# ESCON_Module_64.net
KiCad netlist of a schematic drawn in EAGLE
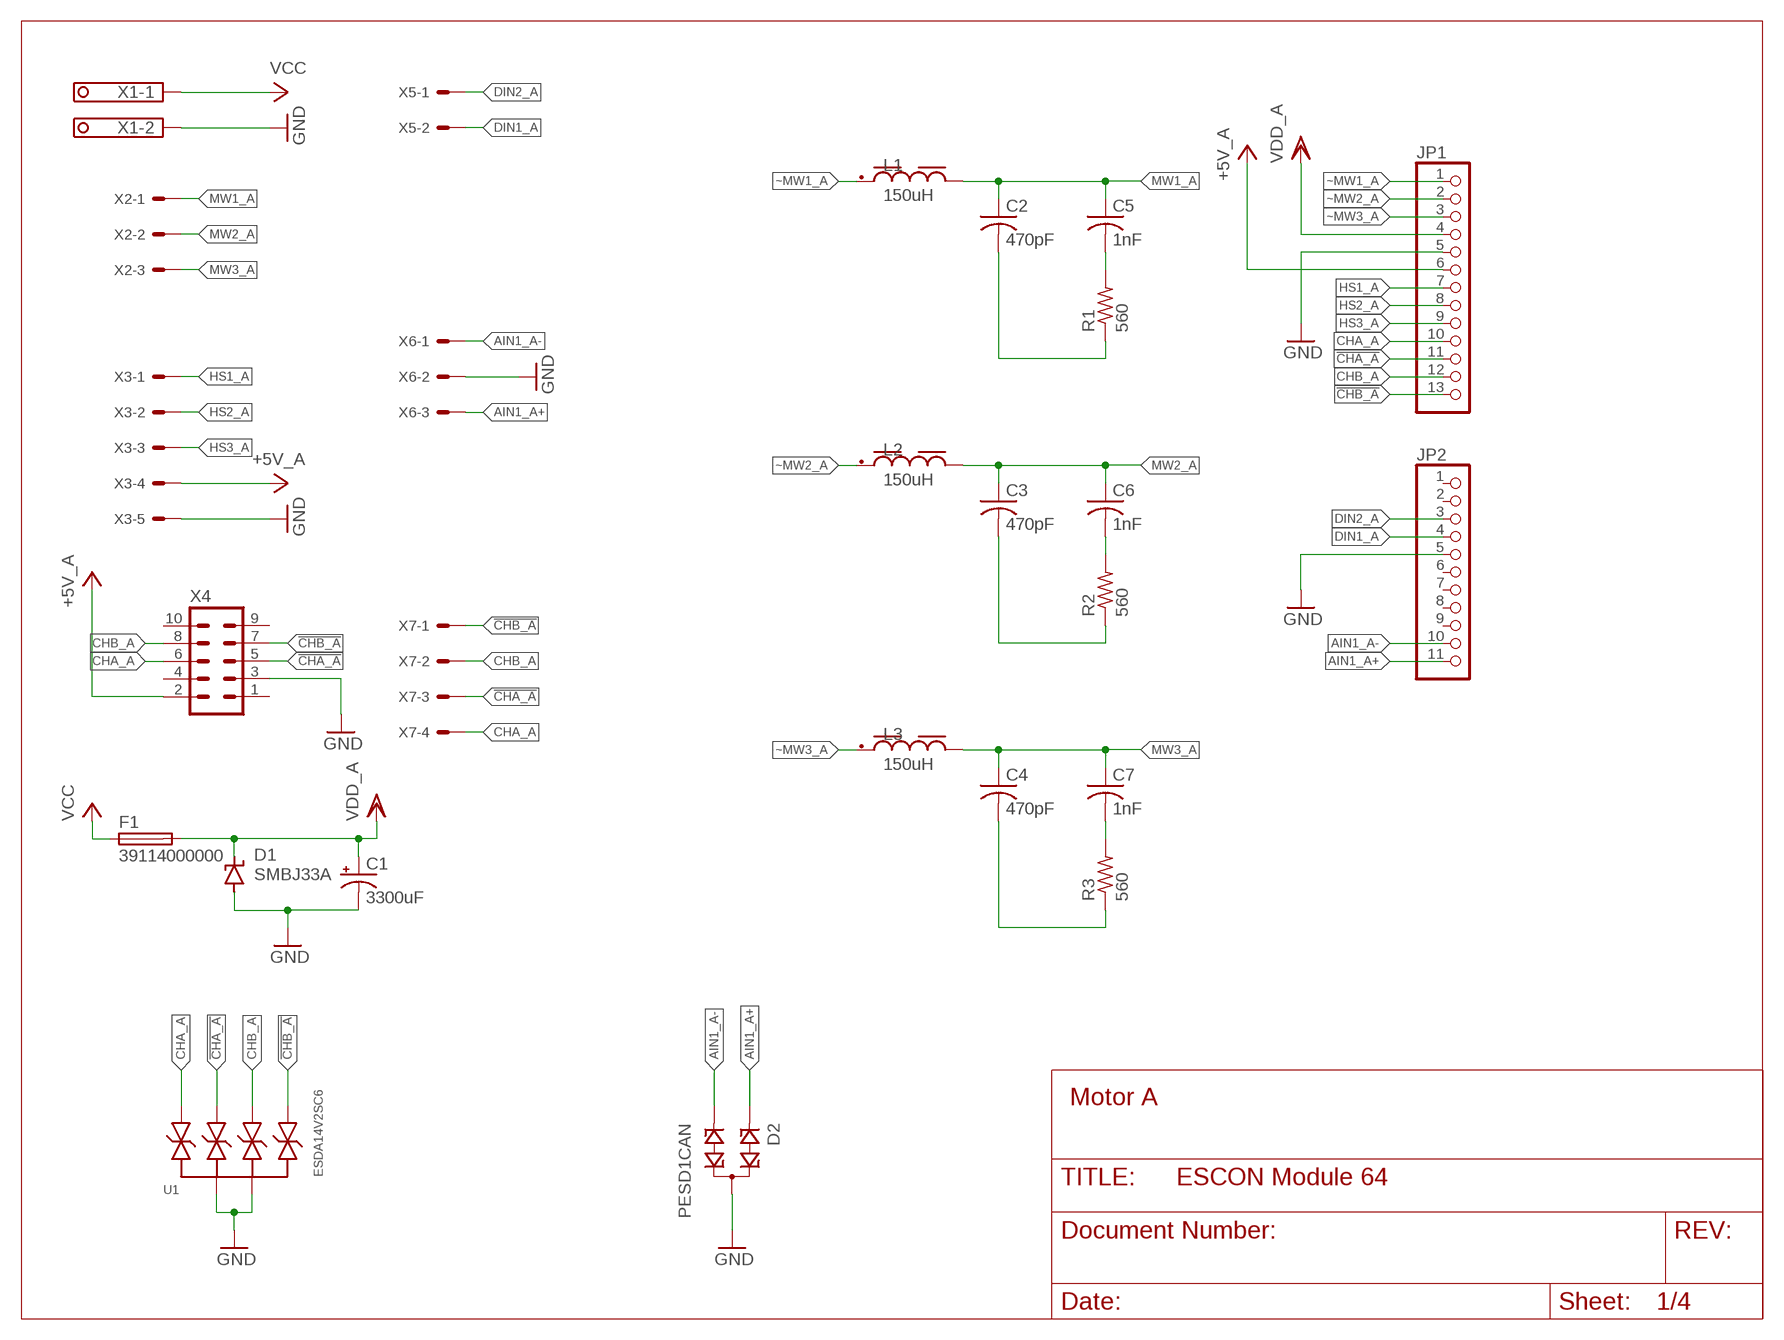
[diagram p0: schematic, sheet 1]
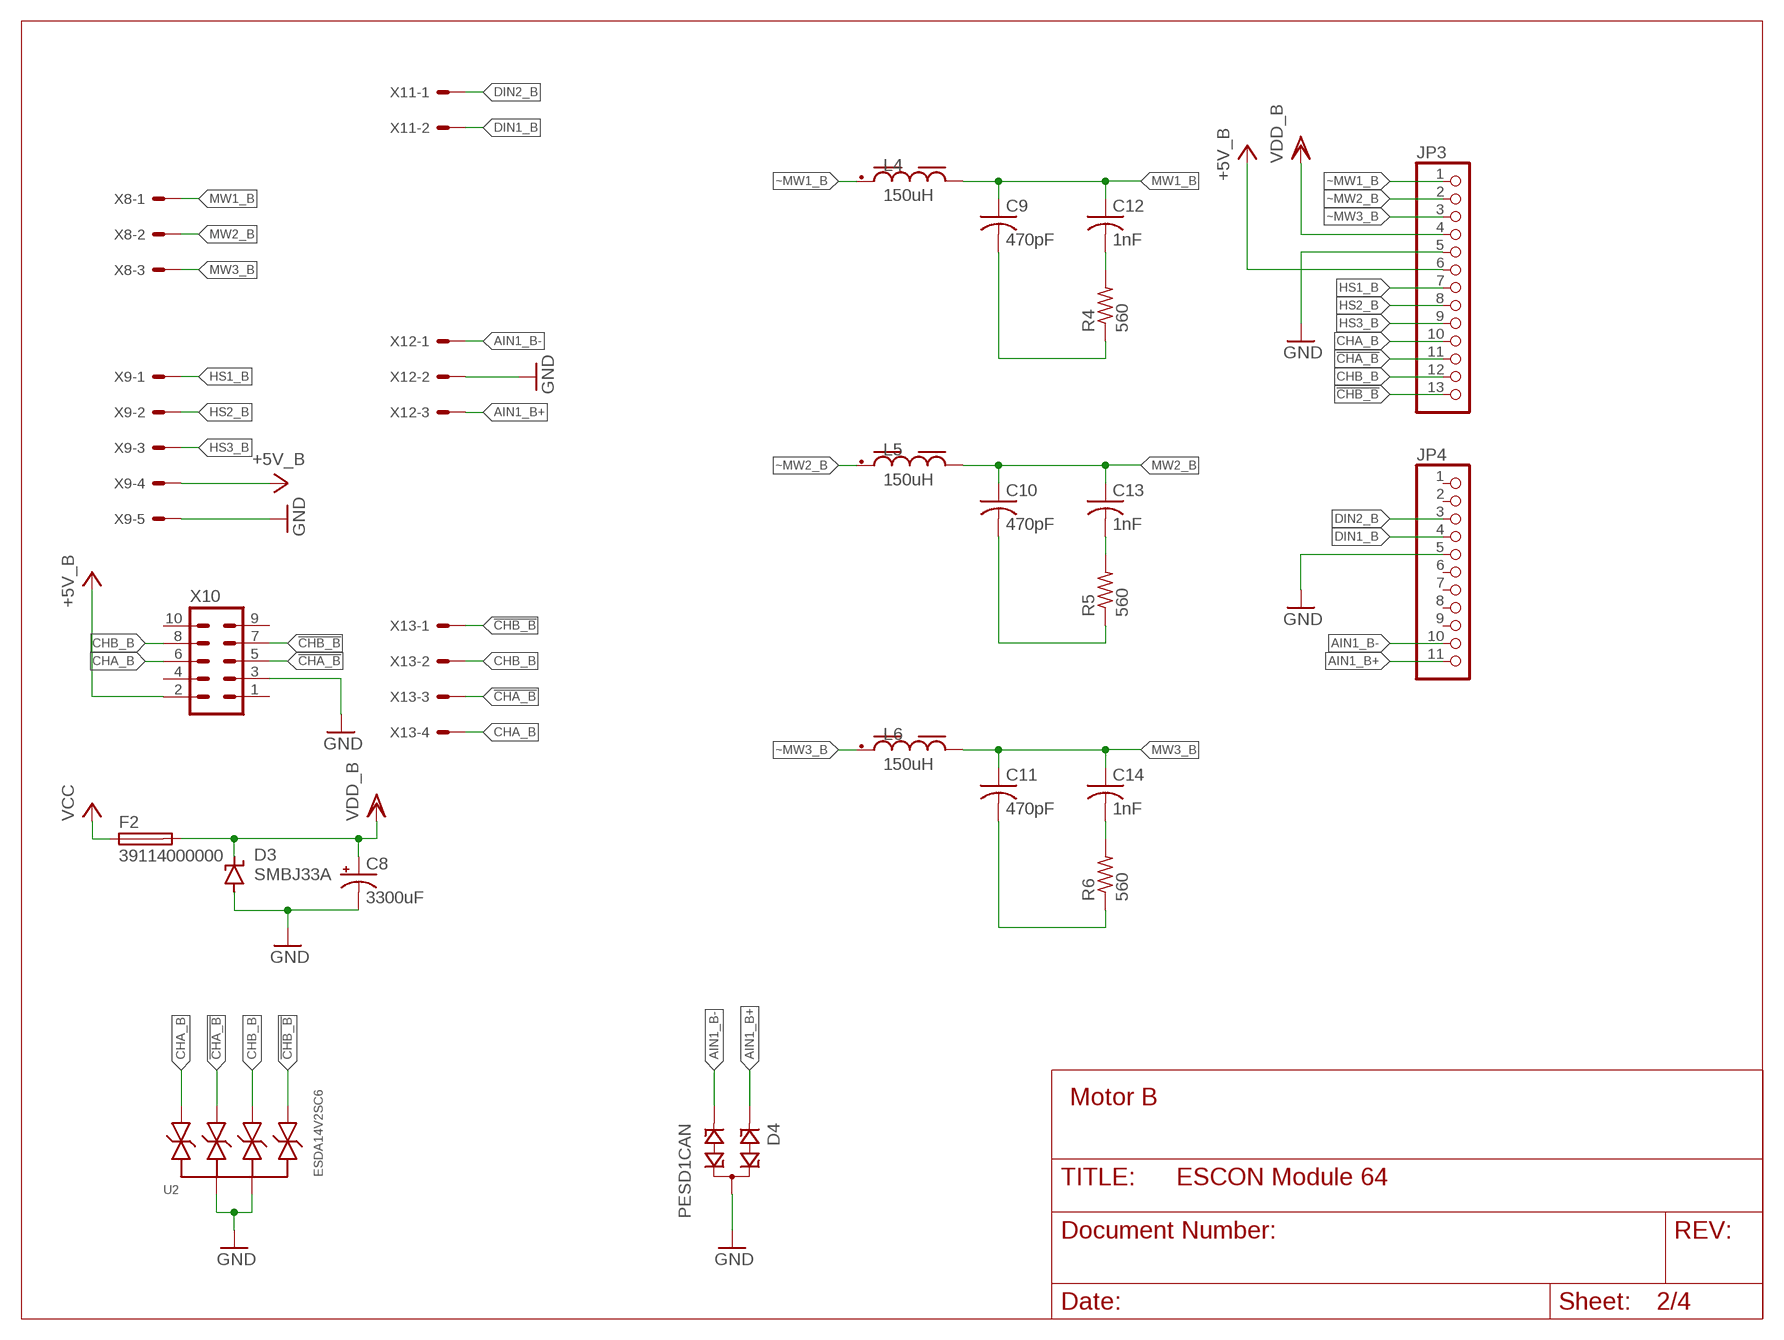
[diagram p1: schematic, sheet 2]
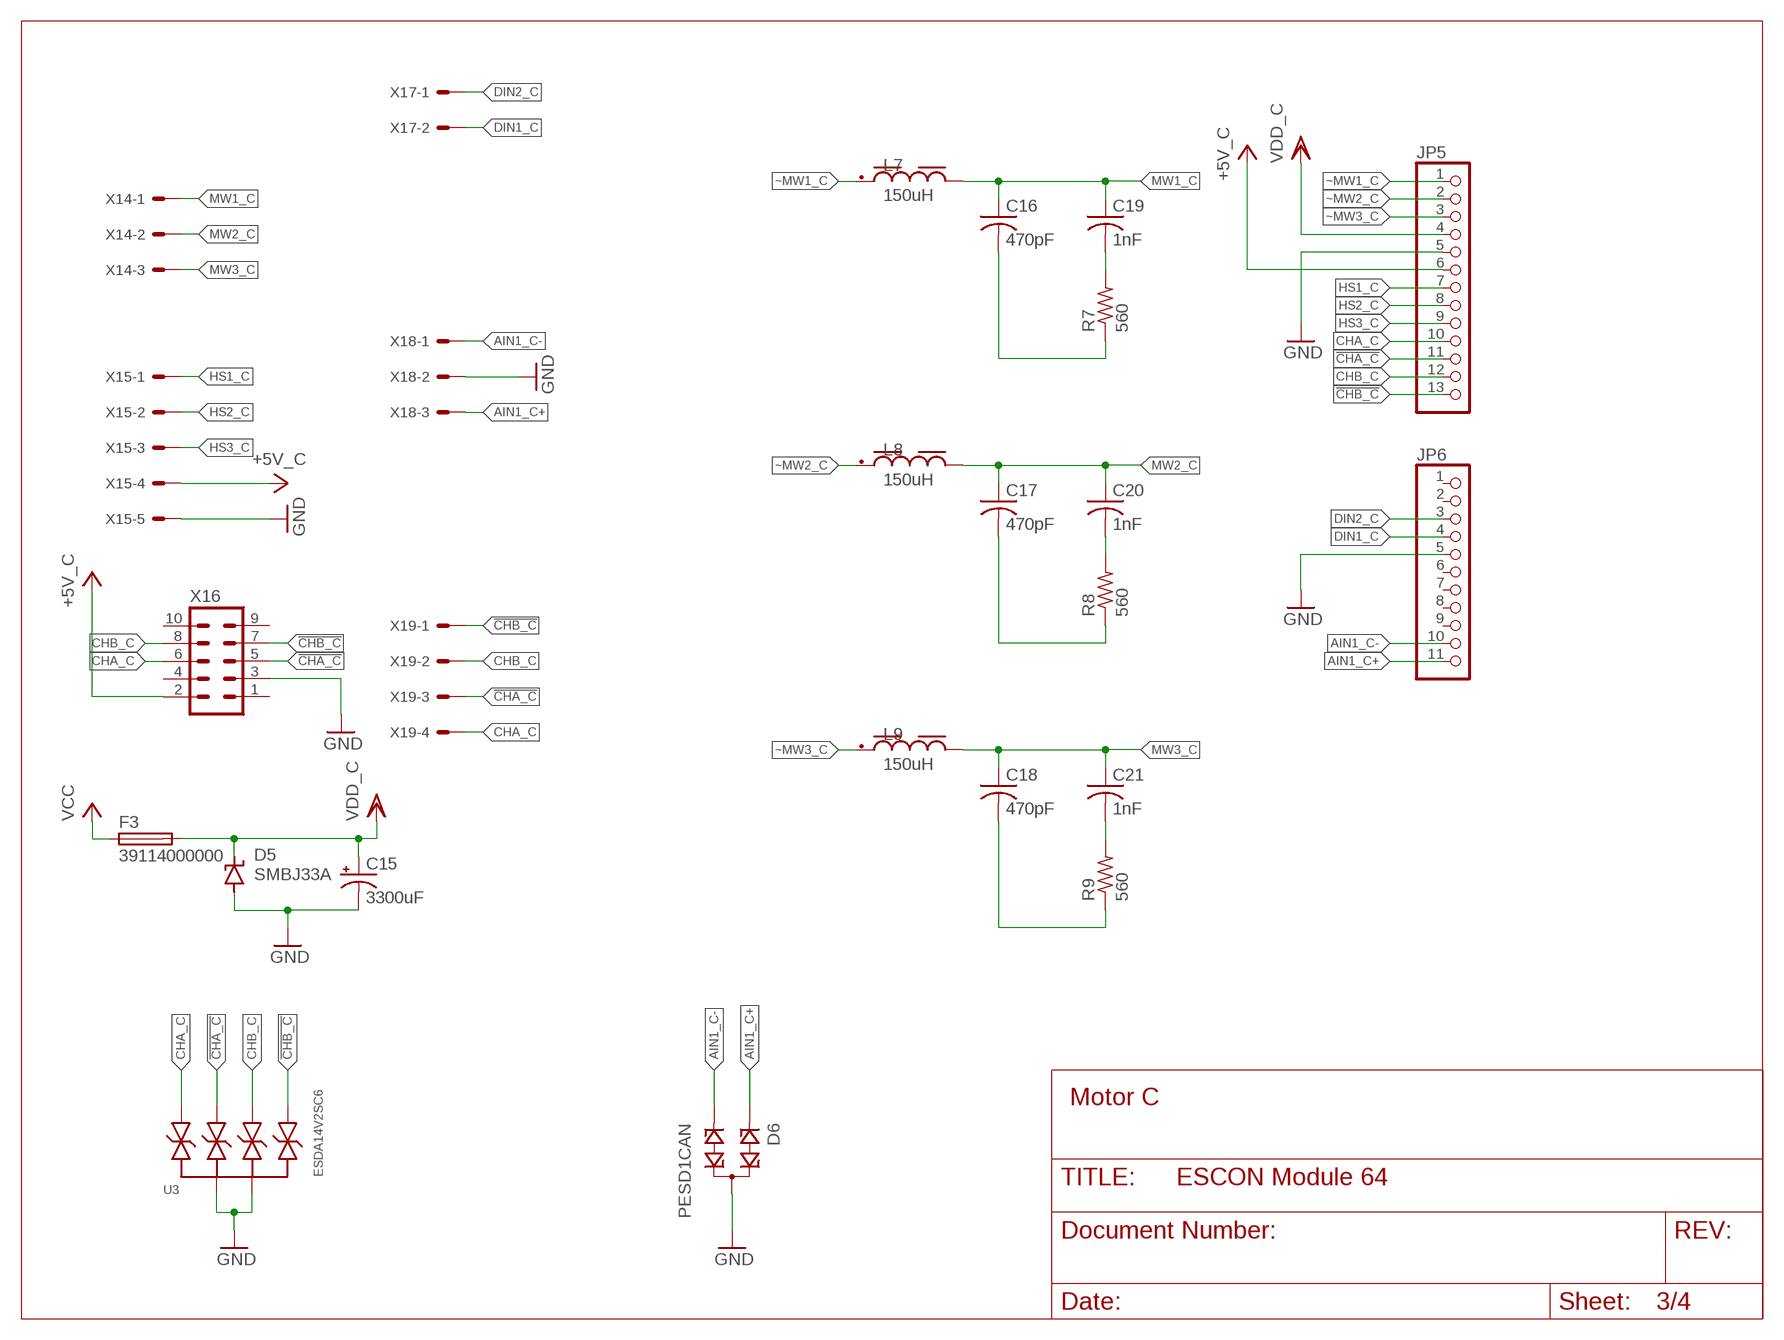
[diagram p2: schematic, sheet 3]
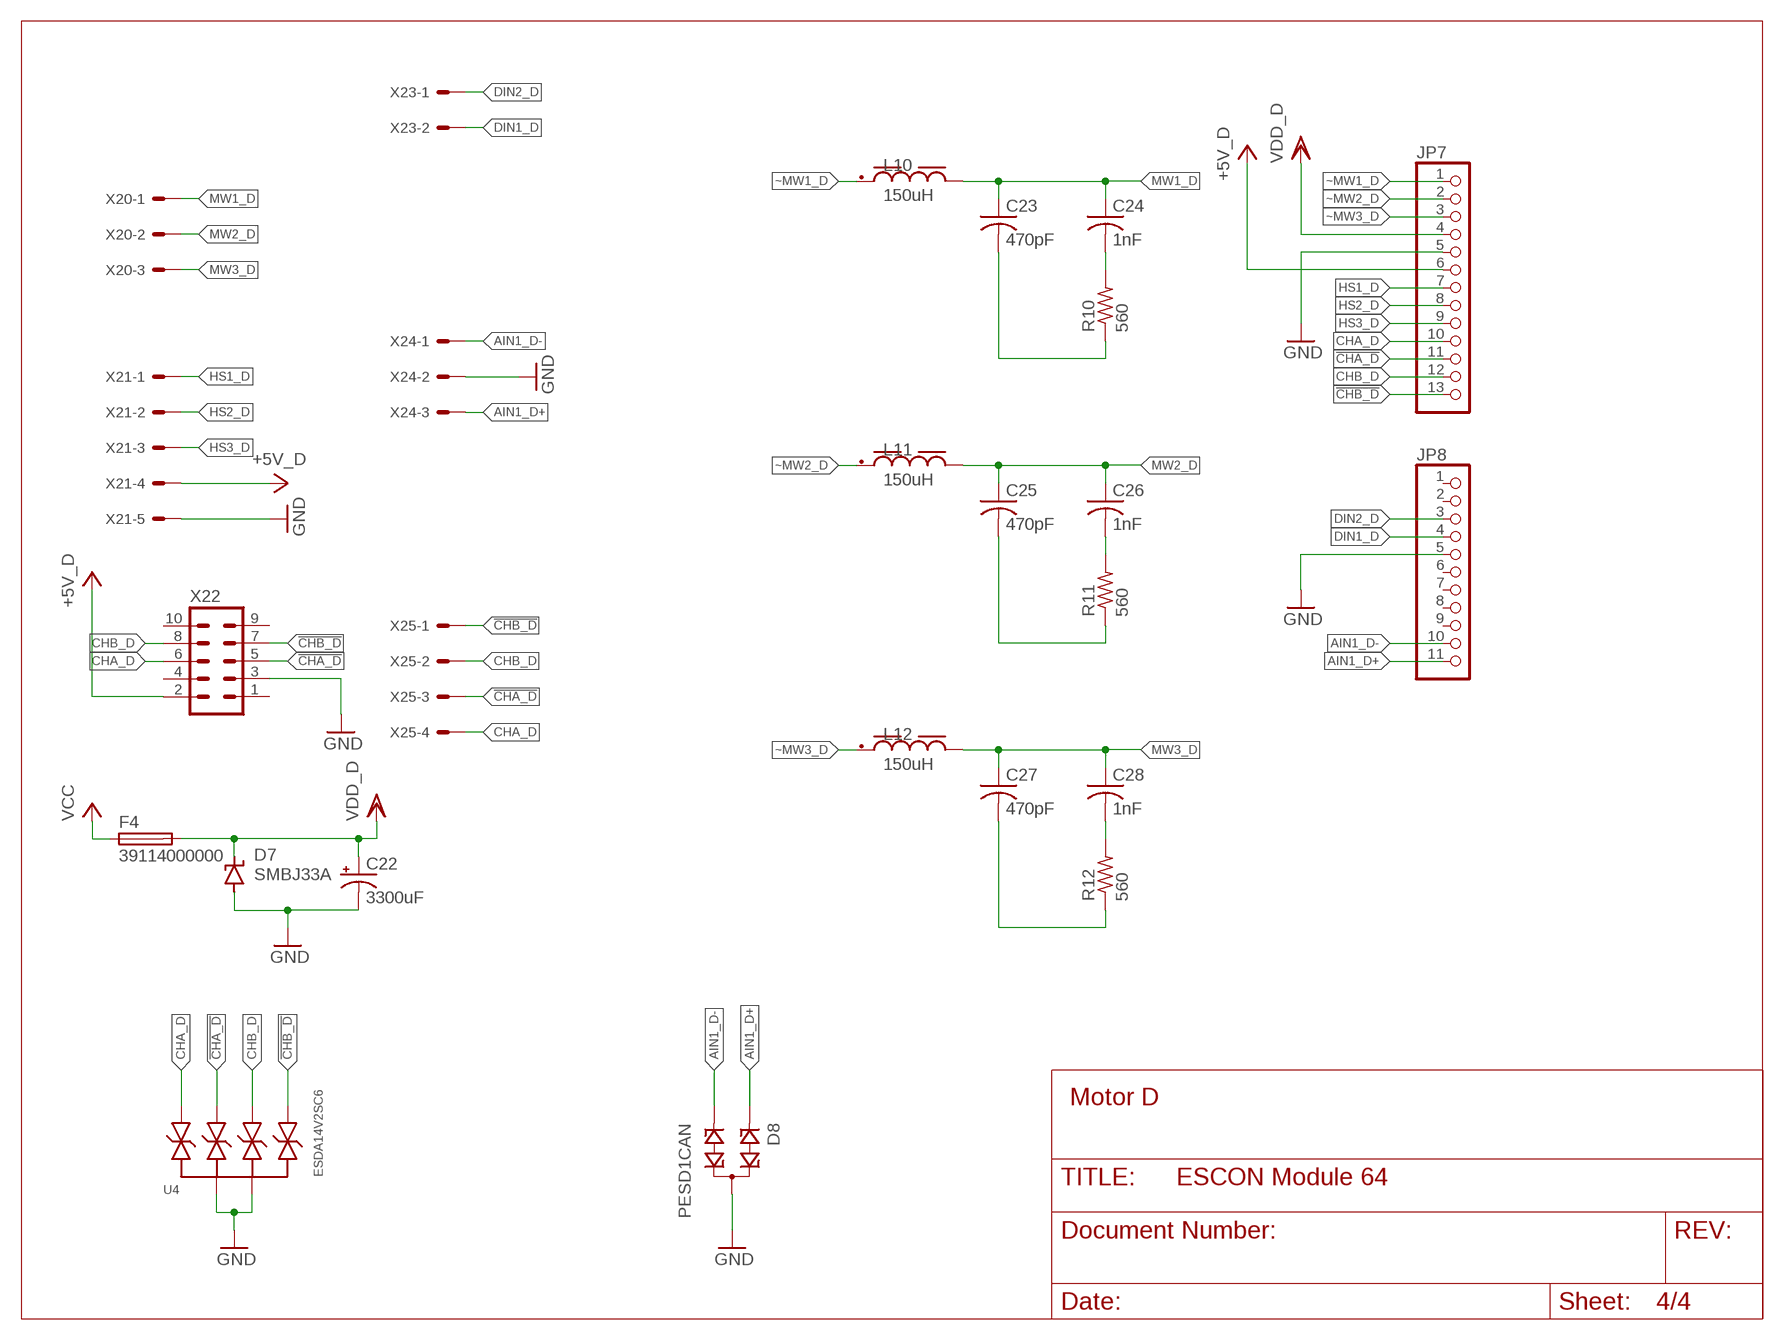
[diagram p3: schematic, sheet 4]

(export (version "E")
  (design (tool "Eeschema 10.0.6"))
  (components
    (comp (ref "C15")
      (value "3300uF")
      (footprint "eagle-import:E7,5-18")
      (libsource (lib "eagle-import") (part "CPOL-USE7.5-18"))
    )
    (comp (ref "C16")
      (value "470pF")
      (footprint "eagle-import:C0603")
      (libsource (lib "eagle-import") (part "C-USC0603"))
    )
    (comp (ref "C17")
      (value "470pF")
      (footprint "eagle-import:C0603")
      (libsource (lib "eagle-import") (part "C-USC0603"))
    )
    (comp (ref "C18")
      (value "470pF")
      (footprint "eagle-import:C0603")
      (libsource (lib "eagle-import") (part "C-USC0603"))
    )
    (comp (ref "C19")
      (value "1nF")
      (footprint "eagle-import:C0603")
      (libsource (lib "eagle-import") (part "C-USC0603"))
    )
    (comp (ref "C20")
      (value "1nF")
      (footprint "eagle-import:C0603")
      (libsource (lib "eagle-import") (part "C-USC0603"))
    )
    (comp (ref "C21")
      (value "1nF")
      (footprint "eagle-import:C0603")
      (libsource (lib "eagle-import") (part "C-USC0603"))
    )
    (comp (ref "D5")
      (value "SMBJ33A")
      (footprint "eagle-import:SMBJ")
      (libsource (lib "eagle-import") (part "SUPPRESSOR-SMBJ"))
    )
    (comp (ref "D6")
      (value "PESD1CAN")
      (footprint "eagle-import:SOT23")
      (libsource (lib "eagle-import") (part "PESD1CAN"))
    )
    (comp (ref "F3")
      (value "39114000000")
      (footprint "eagle-import:TE5")
      (libsource (lib "eagle-import") (part "TE5"))
    )
    (comp (ref "JP5")
      (value "PINHD-1X13")
      (footprint "eagle-import:1X13")
      (libsource (lib "eagle-import") (part "PINHD-1X13"))
    )
    (comp (ref "JP6")
      (value "PINHD-1X11")
      (footprint "eagle-import:1X11")
      (libsource (lib "eagle-import") (part "PINHD-1X11"))
    )
    (comp (ref "L7")
      (value "150uH")
      (footprint "eagle-import:WE-PD_1210")
      (libsource (lib "eagle-import") (part "WE-PD_1210_7447709151"))
    )
    (comp (ref "L8")
      (value "150uH")
      (footprint "eagle-import:WE-PD_1210")
      (libsource (lib "eagle-import") (part "WE-PD_1210_7447709151"))
    )
    (comp (ref "L9")
      (value "150uH")
      (footprint "eagle-import:WE-PD_1210")
      (libsource (lib "eagle-import") (part "WE-PD_1210_7447709151"))
    )
    (comp (ref "R7")
      (value "560")
      (footprint "eagle-import:R0603")
      (libsource (lib "eagle-import") (part "R-US_R0603"))
    )
    (comp (ref "R8")
      (value "560")
      (footprint "eagle-import:R0603")
      (libsource (lib "eagle-import") (part "R-US_R0603"))
    )
    (comp (ref "R9")
      (value "560")
      (footprint "eagle-import:R0603")
      (libsource (lib "eagle-import") (part "R-US_R0603"))
    )
    (comp (ref "U3")
      (value "ESDA14V2SC6")
      (footprint "eagle-import:SOT95P280X145-6N")
      (fields (field (name "MF") "STMicroelectronics"))
      (libsource (lib "eagle-import") (part "ESDA14V2SC6"))
    )
    (comp (ref "X14")
      (value "JST-XH-03-PIN-LONG-PAD")
      (footprint "eagle-import:JST-XH-03-PACKAGE-LONG-PAD")
      (libsource (lib "eagle-import") (part "JST-XH-03-PIN-LONG-PAD"))
    )
    (comp (ref "X15")
      (value "JST-XH-05-PIN-LONG-PAD")
      (footprint "eagle-import:JST-XH-05-PACKAGE-LONG-PAD")
      (libsource (lib "eagle-import") (part "JST-XH-05-PIN-LONG-PAD"))
    )
    (comp (ref "X16")
      (value "ML10LP-V")
      (footprint "eagle-import:10LP-V")
      (libsource (lib "eagle-import") (part "ML10LP-V"))
    )
    (comp (ref "X17")
      (value "JST-XH-02-PIN-LONG-PAD")
      (footprint "eagle-import:JST-XH-02-PACKAGE-LONG-PAD")
      (libsource (lib "eagle-import") (part "JST-XH-02-PIN-LONG-PAD"))
    )
    (comp (ref "X18")
      (value "JST-XH-03-PIN-LONG-PAD")
      (footprint "eagle-import:JST-XH-03-PACKAGE-LONG-PAD")
      (libsource (lib "eagle-import") (part "JST-XH-03-PIN-LONG-PAD"))
    )
    (comp (ref "X19")
      (value "JST-XH-04-PIN-LONG-PAD")
      (footprint "eagle-import:JST-XH-04-PACKAGE-LONG-PAD")
      (libsource (lib "eagle-import") (part "JST-XH-04-PIN-LONG-PAD"))
    )
    (comp (ref "C1")
      (value "3300uF")
      (footprint "eagle-import:E7,5-18")
      (libsource (lib "eagle-import") (part "CPOL-USE7.5-18"))
    )
    (comp (ref "C2")
      (value "470pF")
      (footprint "eagle-import:C0603")
      (libsource (lib "eagle-import") (part "C-USC0603"))
    )
    (comp (ref "C3")
      (value "470pF")
      (footprint "eagle-import:C0603")
      (libsource (lib "eagle-import") (part "C-USC0603"))
    )
    (comp (ref "C4")
      (value "470pF")
      (footprint "eagle-import:C0603")
      (libsource (lib "eagle-import") (part "C-USC0603"))
    )
    (comp (ref "C5")
      (value "1nF")
      (footprint "eagle-import:C0603")
      (libsource (lib "eagle-import") (part "C-USC0603"))
    )
    (comp (ref "C6")
      (value "1nF")
      (footprint "eagle-import:C0603")
      (libsource (lib "eagle-import") (part "C-USC0603"))
    )
    (comp (ref "C7")
      (value "1nF")
      (footprint "eagle-import:C0603")
      (libsource (lib "eagle-import") (part "C-USC0603"))
    )
    (comp (ref "D1")
      (value "SMBJ33A")
      (footprint "eagle-import:SMBJ")
      (libsource (lib "eagle-import") (part "SUPPRESSOR-SMBJ"))
    )
    (comp (ref "D2")
      (value "PESD1CAN")
      (footprint "eagle-import:SOT23")
      (libsource (lib "eagle-import") (part "PESD1CAN"))
    )
    (comp (ref "F1")
      (value "39114000000")
      (footprint "eagle-import:TE5")
      (libsource (lib "eagle-import") (part "TE5"))
    )
    (comp (ref "JP1")
      (value "PINHD-1X13")
      (footprint "eagle-import:1X13")
      (libsource (lib "eagle-import") (part "PINHD-1X13"))
    )
    (comp (ref "JP2")
      (value "PINHD-1X11")
      (footprint "eagle-import:1X11")
      (libsource (lib "eagle-import") (part "PINHD-1X11"))
    )
    (comp (ref "L1")
      (value "150uH")
      (footprint "eagle-import:WE-PD_1210")
      (libsource (lib "eagle-import") (part "WE-PD_1210_7447709151"))
    )
    (comp (ref "L2")
      (value "150uH")
      (footprint "eagle-import:WE-PD_1210")
      (libsource (lib "eagle-import") (part "WE-PD_1210_7447709151"))
    )
    (comp (ref "L3")
      (value "150uH")
      (footprint "eagle-import:WE-PD_1210")
      (libsource (lib "eagle-import") (part "WE-PD_1210_7447709151"))
    )
    (comp (ref "R1")
      (value "560")
      (footprint "eagle-import:R0603")
      (libsource (lib "eagle-import") (part "R-US_R0603"))
    )
    (comp (ref "R2")
      (value "560")
      (footprint "eagle-import:R0603")
      (libsource (lib "eagle-import") (part "R-US_R0603"))
    )
    (comp (ref "R3")
      (value "560")
      (footprint "eagle-import:R0603")
      (libsource (lib "eagle-import") (part "R-US_R0603"))
    )
    (comp (ref "U1")
      (value "ESDA14V2SC6")
      (footprint "eagle-import:SOT95P280X145-6N")
      (fields (field (name "MF") "STMicroelectronics"))
      (libsource (lib "eagle-import") (part "ESDA14V2SC6"))
    )
    (comp (ref "X1")
      (value "TERMINAL-BLOCK-3.5MM-2-PIN-LONG-PAD")
      (footprint "eagle-import:TERMINAL-BLOCK-2-PIN-3.5MM-LONG-PAD")
      (libsource (lib "eagle-import") (part "TERMINAL-BLOCK-3.5MM-2-PIN-LONG-PAD"))
    )
    (comp (ref "X2")
      (value "JST-XH-03-PIN-LONG-PAD")
      (footprint "eagle-import:JST-XH-03-PACKAGE-LONG-PAD")
      (libsource (lib "eagle-import") (part "JST-XH-03-PIN-LONG-PAD"))
    )
    (comp (ref "X3")
      (value "JST-XH-05-PIN-LONG-PAD")
      (footprint "eagle-import:JST-XH-05-PACKAGE-LONG-PAD")
      (libsource (lib "eagle-import") (part "JST-XH-05-PIN-LONG-PAD"))
    )
    (comp (ref "X4")
      (value "ML10LP-V")
      (footprint "eagle-import:10LP-V")
      (libsource (lib "eagle-import") (part "ML10LP-V"))
    )
    (comp (ref "X5")
      (value "JST-XH-02-PIN-LONG-PAD")
      (footprint "eagle-import:JST-XH-02-PACKAGE-LONG-PAD")
      (libsource (lib "eagle-import") (part "JST-XH-02-PIN-LONG-PAD"))
    )
    (comp (ref "X6")
      (value "JST-XH-03-PIN-LONG-PAD")
      (footprint "eagle-import:JST-XH-03-PACKAGE-LONG-PAD")
      (libsource (lib "eagle-import") (part "JST-XH-03-PIN-LONG-PAD"))
    )
    (comp (ref "X7")
      (value "JST-XH-04-PIN-LONG-PAD")
      (footprint "eagle-import:JST-XH-04-PACKAGE-LONG-PAD")
      (libsource (lib "eagle-import") (part "JST-XH-04-PIN-LONG-PAD"))
    )
    (comp (ref "C8")
      (value "3300uF")
      (footprint "eagle-import:E7,5-18")
      (libsource (lib "eagle-import") (part "CPOL-USE7.5-18"))
    )
    (comp (ref "C9")
      (value "470pF")
      (footprint "eagle-import:C0603")
      (libsource (lib "eagle-import") (part "C-USC0603"))
    )
    (comp (ref "C10")
      (value "470pF")
      (footprint "eagle-import:C0603")
      (libsource (lib "eagle-import") (part "C-USC0603"))
    )
    (comp (ref "C11")
      (value "470pF")
      (footprint "eagle-import:C0603")
      (libsource (lib "eagle-import") (part "C-USC0603"))
    )
    (comp (ref "C12")
      (value "1nF")
      (footprint "eagle-import:C0603")
      (libsource (lib "eagle-import") (part "C-USC0603"))
    )
    (comp (ref "C13")
      (value "1nF")
      (footprint "eagle-import:C0603")
      (libsource (lib "eagle-import") (part "C-USC0603"))
    )
    (comp (ref "C14")
      (value "1nF")
      (footprint "eagle-import:C0603")
      (libsource (lib "eagle-import") (part "C-USC0603"))
    )
    (comp (ref "D3")
      (value "SMBJ33A")
      (footprint "eagle-import:SMBJ")
      (libsource (lib "eagle-import") (part "SUPPRESSOR-SMBJ"))
    )
    (comp (ref "D4")
      (value "PESD1CAN")
      (footprint "eagle-import:SOT23")
      (libsource (lib "eagle-import") (part "PESD1CAN"))
    )
    (comp (ref "F2")
      (value "39114000000")
      (footprint "eagle-import:TE5")
      (libsource (lib "eagle-import") (part "TE5"))
    )
    (comp (ref "JP3")
      (value "PINHD-1X13")
      (footprint "eagle-import:1X13")
      (libsource (lib "eagle-import") (part "PINHD-1X13"))
    )
    (comp (ref "JP4")
      (value "PINHD-1X11")
      (footprint "eagle-import:1X11")
      (libsource (lib "eagle-import") (part "PINHD-1X11"))
    )
    (comp (ref "L4")
      (value "150uH")
      (footprint "eagle-import:WE-PD_1210")
      (libsource (lib "eagle-import") (part "WE-PD_1210_7447709151"))
    )
    (comp (ref "L5")
      (value "150uH")
      (footprint "eagle-import:WE-PD_1210")
      (libsource (lib "eagle-import") (part "WE-PD_1210_7447709151"))
    )
    (comp (ref "L6")
      (value "150uH")
      (footprint "eagle-import:WE-PD_1210")
      (libsource (lib "eagle-import") (part "WE-PD_1210_7447709151"))
    )
    (comp (ref "R4")
      (value "560")
      (footprint "eagle-import:R0603")
      (libsource (lib "eagle-import") (part "R-US_R0603"))
    )
    (comp (ref "R5")
      (value "560")
      (footprint "eagle-import:R0603")
      (libsource (lib "eagle-import") (part "R-US_R0603"))
    )
    (comp (ref "R6")
      (value "560")
      (footprint "eagle-import:R0603")
      (libsource (lib "eagle-import") (part "R-US_R0603"))
    )
    (comp (ref "U2")
      (value "ESDA14V2SC6")
      (footprint "eagle-import:SOT95P280X145-6N")
      (fields (field (name "MF") "STMicroelectronics"))
      (libsource (lib "eagle-import") (part "ESDA14V2SC6"))
    )
    (comp (ref "X8")
      (value "JST-XH-03-PIN-LONG-PAD")
      (footprint "eagle-import:JST-XH-03-PACKAGE-LONG-PAD")
      (libsource (lib "eagle-import") (part "JST-XH-03-PIN-LONG-PAD"))
    )
    (comp (ref "X9")
      (value "JST-XH-05-PIN-LONG-PAD")
      (footprint "eagle-import:JST-XH-05-PACKAGE-LONG-PAD")
      (libsource (lib "eagle-import") (part "JST-XH-05-PIN-LONG-PAD"))
    )
    (comp (ref "X10")
      (value "ML10LP-V")
      (footprint "eagle-import:10LP-V")
      (libsource (lib "eagle-import") (part "ML10LP-V"))
    )
    (comp (ref "X11")
      (value "JST-XH-02-PIN-LONG-PAD")
      (footprint "eagle-import:JST-XH-02-PACKAGE-LONG-PAD")
      (libsource (lib "eagle-import") (part "JST-XH-02-PIN-LONG-PAD"))
    )
    (comp (ref "X12")
      (value "JST-XH-03-PIN-LONG-PAD")
      (footprint "eagle-import:JST-XH-03-PACKAGE-LONG-PAD")
      (libsource (lib "eagle-import") (part "JST-XH-03-PIN-LONG-PAD"))
    )
    (comp (ref "X13")
      (value "JST-XH-04-PIN-LONG-PAD")
      (footprint "eagle-import:JST-XH-04-PACKAGE-LONG-PAD")
      (libsource (lib "eagle-import") (part "JST-XH-04-PIN-LONG-PAD"))
    )
    (comp (ref "C22")
      (value "3300uF")
      (footprint "eagle-import:E7,5-18")
      (libsource (lib "eagle-import") (part "CPOL-USE7.5-18"))
    )
    (comp (ref "C23")
      (value "470pF")
      (footprint "eagle-import:C0603")
      (libsource (lib "eagle-import") (part "C-USC0603"))
    )
    (comp (ref "C24")
      (value "1nF")
      (footprint "eagle-import:C0603")
      (libsource (lib "eagle-import") (part "C-USC0603"))
    )
    (comp (ref "C25")
      (value "470pF")
      (footprint "eagle-import:C0603")
      (libsource (lib "eagle-import") (part "C-USC0603"))
    )
    (comp (ref "C26")
      (value "1nF")
      (footprint "eagle-import:C0603")
      (libsource (lib "eagle-import") (part "C-USC0603"))
    )
    (comp (ref "C27")
      (value "470pF")
      (footprint "eagle-import:C0603")
      (libsource (lib "eagle-import") (part "C-USC0603"))
    )
    (comp (ref "C28")
      (value "1nF")
      (footprint "eagle-import:C0603")
      (libsource (lib "eagle-import") (part "C-USC0603"))
    )
    (comp (ref "D7")
      (value "SMBJ33A")
      (footprint "eagle-import:SMBJ")
      (libsource (lib "eagle-import") (part "SUPPRESSOR-SMBJ"))
    )
    (comp (ref "D8")
      (value "PESD1CAN")
      (footprint "eagle-import:SOT23")
      (libsource (lib "eagle-import") (part "PESD1CAN"))
    )
    (comp (ref "F4")
      (value "39114000000")
      (footprint "eagle-import:TE5")
      (libsource (lib "eagle-import") (part "TE5"))
    )
    (comp (ref "JP7")
      (value "PINHD-1X13")
      (footprint "eagle-import:1X13")
      (libsource (lib "eagle-import") (part "PINHD-1X13"))
    )
    (comp (ref "JP8")
      (value "PINHD-1X11")
      (footprint "eagle-import:1X11")
      (libsource (lib "eagle-import") (part "PINHD-1X11"))
    )
    (comp (ref "L10")
      (value "150uH")
      (footprint "eagle-import:WE-PD_1210")
      (libsource (lib "eagle-import") (part "WE-PD_1210_7447709151"))
    )
    (comp (ref "L11")
      (value "150uH")
      (footprint "eagle-import:WE-PD_1210")
      (libsource (lib "eagle-import") (part "WE-PD_1210_7447709151"))
    )
    (comp (ref "L12")
      (value "150uH")
      (footprint "eagle-import:WE-PD_1210")
      (libsource (lib "eagle-import") (part "WE-PD_1210_7447709151"))
    )
    (comp (ref "R10")
      (value "560")
      (footprint "eagle-import:R0603")
      (libsource (lib "eagle-import") (part "R-US_R0603"))
    )
    (comp (ref "R11")
      (value "560")
      (footprint "eagle-import:R0603")
      (libsource (lib "eagle-import") (part "R-US_R0603"))
    )
    (comp (ref "R12")
      (value "560")
      (footprint "eagle-import:R0603")
      (libsource (lib "eagle-import") (part "R-US_R0603"))
    )
    (comp (ref "U4")
      (value "ESDA14V2SC6")
      (footprint "eagle-import:SOT95P280X145-6N")
      (fields (field (name "MF") "STMicroelectronics"))
      (libsource (lib "eagle-import") (part "ESDA14V2SC6"))
    )
    (comp (ref "X20")
      (value "JST-XH-03-PIN-LONG-PAD")
      (footprint "eagle-import:JST-XH-03-PACKAGE-LONG-PAD")
      (libsource (lib "eagle-import") (part "JST-XH-03-PIN-LONG-PAD"))
    )
    (comp (ref "X21")
      (value "JST-XH-05-PIN-LONG-PAD")
      (footprint "eagle-import:JST-XH-05-PACKAGE-LONG-PAD")
      (libsource (lib "eagle-import") (part "JST-XH-05-PIN-LONG-PAD"))
    )
    (comp (ref "X22")
      (value "ML10LP-V")
      (footprint "eagle-import:10LP-V")
      (libsource (lib "eagle-import") (part "ML10LP-V"))
    )
    (comp (ref "X23")
      (value "JST-XH-02-PIN-LONG-PAD")
      (footprint "eagle-import:JST-XH-02-PACKAGE-LONG-PAD")
      (libsource (lib "eagle-import") (part "JST-XH-02-PIN-LONG-PAD"))
    )
    (comp (ref "X24")
      (value "JST-XH-03-PIN-LONG-PAD")
      (footprint "eagle-import:JST-XH-03-PACKAGE-LONG-PAD")
      (libsource (lib "eagle-import") (part "JST-XH-03-PIN-LONG-PAD"))
    )
    (comp (ref "X25")
      (value "JST-XH-04-PIN-LONG-PAD")
      (footprint "eagle-import:JST-XH-04-PACKAGE-LONG-PAD")
      (libsource (lib "eagle-import") (part "JST-XH-04-PIN-LONG-PAD"))
    )
  )
  (nets
    (net (code "1") (name "+5V_A") (class "Default")
      (node (ref "JP1") (pin "6") (pinfunction "6_6") (pintype "passive"))
      (node (ref "X3") (pin "4") (pinfunction "S_4") (pintype "passive"))
      (node (ref "X4") (pin "2") (pinfunction "2_2") (pintype "bidirectional"))
    )
    (net (code "2") (name "+5V_B") (class "Default")
      (node (ref "JP3") (pin "6") (pinfunction "6_6") (pintype "passive"))
      (node (ref "X10") (pin "2") (pinfunction "2_2") (pintype "bidirectional"))
      (node (ref "X9") (pin "4") (pinfunction "S_4") (pintype "passive"))
    )
    (net (code "3") (name "+5V_C") (class "Default")
      (node (ref "JP5") (pin "6") (pinfunction "6_6") (pintype "passive"))
      (node (ref "X15") (pin "4") (pinfunction "S_4") (pintype "passive"))
      (node (ref "X16") (pin "2") (pinfunction "2_2") (pintype "bidirectional"))
    )
    (net (code "4") (name "+5V_D") (class "Default")
      (node (ref "JP7") (pin "6") (pinfunction "6_6") (pintype "passive"))
      (node (ref "X21") (pin "4") (pinfunction "S_4") (pintype "passive"))
      (node (ref "X22") (pin "2") (pinfunction "2_2") (pintype "bidirectional"))
    )
    (net (code "5") (name "AIN1_A+") (class "Default")
      (node (ref "D2") (pin "1") (pinfunction "1_1") (pintype "passive"))
      (node (ref "JP2") (pin "11") (pinfunction "11_11") (pintype "passive"))
      (node (ref "X6") (pin "3") (pinfunction "S_3") (pintype "passive"))
    )
    (net (code "6") (name "AIN1_A-") (class "Default")
      (node (ref "D2") (pin "2") (pinfunction "2_2") (pintype "passive"))
      (node (ref "JP2") (pin "10") (pinfunction "10_10") (pintype "passive"))
      (node (ref "X6") (pin "1") (pinfunction "S_1") (pintype "passive"))
    )
    (net (code "7") (name "AIN1_B+") (class "Default")
      (node (ref "D4") (pin "1") (pinfunction "1_1") (pintype "passive"))
      (node (ref "JP4") (pin "11") (pinfunction "11_11") (pintype "passive"))
      (node (ref "X12") (pin "3") (pinfunction "S_3") (pintype "passive"))
    )
    (net (code "8") (name "AIN1_B-") (class "Default")
      (node (ref "D4") (pin "2") (pinfunction "2_2") (pintype "passive"))
      (node (ref "JP4") (pin "10") (pinfunction "10_10") (pintype "passive"))
      (node (ref "X12") (pin "1") (pinfunction "S_1") (pintype "passive"))
    )
    (net (code "9") (name "AIN1_C+") (class "Default")
      (node (ref "D6") (pin "1") (pinfunction "1_1") (pintype "passive"))
      (node (ref "JP6") (pin "11") (pinfunction "11_11") (pintype "passive"))
      (node (ref "X18") (pin "3") (pinfunction "S_3") (pintype "passive"))
    )
    (net (code "10") (name "AIN1_C-") (class "Default")
      (node (ref "D6") (pin "2") (pinfunction "2_2") (pintype "passive"))
      (node (ref "JP6") (pin "10") (pinfunction "10_10") (pintype "passive"))
      (node (ref "X18") (pin "1") (pinfunction "S_1") (pintype "passive"))
    )
    (net (code "11") (name "AIN1_D+") (class "Default")
      (node (ref "D8") (pin "1") (pinfunction "1_1") (pintype "passive"))
      (node (ref "JP8") (pin "11") (pinfunction "11_11") (pintype "passive"))
      (node (ref "X24") (pin "3") (pinfunction "S_3") (pintype "passive"))
    )
    (net (code "12") (name "AIN1_D-") (class "Default")
      (node (ref "D8") (pin "2") (pinfunction "2_2") (pintype "passive"))
      (node (ref "JP8") (pin "10") (pinfunction "10_10") (pintype "passive"))
      (node (ref "X24") (pin "1") (pinfunction "S_1") (pintype "passive"))
    )
    (net (code "13") (name "CHA_A") (class "Default")
      (node (ref "JP1") (pin "10") (pinfunction "10_10") (pintype "passive"))
      (node (ref "U1") (pin "1") (pinfunction "1_1") (pintype "passive"))
      (node (ref "X4") (pin "6") (pinfunction "6_6") (pintype "bidirectional"))
      (node (ref "X7") (pin "4") (pinfunction "S_4") (pintype "passive"))
    )
    (net (code "14") (name "CHA_B") (class "Default")
      (node (ref "JP3") (pin "10") (pinfunction "10_10") (pintype "passive"))
      (node (ref "U2") (pin "1") (pinfunction "1_1") (pintype "passive"))
      (node (ref "X10") (pin "6") (pinfunction "6_6") (pintype "bidirectional"))
      (node (ref "X13") (pin "4") (pinfunction "S_4") (pintype "passive"))
    )
    (net (code "15") (name "CHA_C") (class "Default")
      (node (ref "JP5") (pin "10") (pinfunction "10_10") (pintype "passive"))
      (node (ref "U3") (pin "1") (pinfunction "1_1") (pintype "passive"))
      (node (ref "X16") (pin "6") (pinfunction "6_6") (pintype "bidirectional"))
      (node (ref "X19") (pin "4") (pinfunction "S_4") (pintype "passive"))
    )
    (net (code "16") (name "CHA_D") (class "Default")
      (node (ref "JP7") (pin "10") (pinfunction "10_10") (pintype "passive"))
      (node (ref "U4") (pin "1") (pinfunction "1_1") (pintype "passive"))
      (node (ref "X22") (pin "6") (pinfunction "6_6") (pintype "bidirectional"))
      (node (ref "X25") (pin "4") (pinfunction "S_4") (pintype "passive"))
    )
    (net (code "17") (name "CHB_A") (class "Default")
      (node (ref "JP1") (pin "12") (pinfunction "12_12") (pintype "passive"))
      (node (ref "U1") (pin "4") (pinfunction "4_4") (pintype "passive"))
      (node (ref "X4") (pin "8") (pinfunction "8_8") (pintype "bidirectional"))
      (node (ref "X7") (pin "2") (pinfunction "S_2") (pintype "passive"))
    )
    (net (code "18") (name "CHB_B") (class "Default")
      (node (ref "JP3") (pin "12") (pinfunction "12_12") (pintype "passive"))
      (node (ref "U2") (pin "4") (pinfunction "4_4") (pintype "passive"))
      (node (ref "X10") (pin "8") (pinfunction "8_8") (pintype "bidirectional"))
      (node (ref "X13") (pin "2") (pinfunction "S_2") (pintype "passive"))
    )
    (net (code "19") (name "CHB_C") (class "Default")
      (node (ref "JP5") (pin "12") (pinfunction "12_12") (pintype "passive"))
      (node (ref "U3") (pin "4") (pinfunction "4_4") (pintype "passive"))
      (node (ref "X16") (pin "8") (pinfunction "8_8") (pintype "bidirectional"))
      (node (ref "X19") (pin "2") (pinfunction "S_2") (pintype "passive"))
    )
    (net (code "20") (name "CHB_D") (class "Default")
      (node (ref "JP7") (pin "12") (pinfunction "12_12") (pintype "passive"))
      (node (ref "U4") (pin "4") (pinfunction "4_4") (pintype "passive"))
      (node (ref "X22") (pin "8") (pinfunction "8_8") (pintype "bidirectional"))
      (node (ref "X25") (pin "2") (pinfunction "S_2") (pintype "passive"))
    )
    (net (code "21") (name "DIN1_A") (class "Default")
      (node (ref "JP2") (pin "4") (pinfunction "4_4") (pintype "passive"))
      (node (ref "X5") (pin "2") (pinfunction "S_2") (pintype "passive"))
    )
    (net (code "22") (name "DIN1_B") (class "Default")
      (node (ref "JP4") (pin "4") (pinfunction "4_4") (pintype "passive"))
      (node (ref "X11") (pin "2") (pinfunction "S_2") (pintype "passive"))
    )
    (net (code "23") (name "DIN1_C") (class "Default")
      (node (ref "JP6") (pin "4") (pinfunction "4_4") (pintype "passive"))
      (node (ref "X17") (pin "2") (pinfunction "S_2") (pintype "passive"))
    )
    (net (code "24") (name "DIN1_D") (class "Default")
      (node (ref "JP8") (pin "4") (pinfunction "4_4") (pintype "passive"))
      (node (ref "X23") (pin "2") (pinfunction "S_2") (pintype "passive"))
    )
    (net (code "25") (name "DIN2_A") (class "Default")
      (node (ref "JP2") (pin "3") (pinfunction "3_3") (pintype "passive"))
      (node (ref "X5") (pin "1") (pinfunction "S_1") (pintype "passive"))
    )
    (net (code "26") (name "DIN2_B") (class "Default")
      (node (ref "JP4") (pin "3") (pinfunction "3_3") (pintype "passive"))
      (node (ref "X11") (pin "1") (pinfunction "S_1") (pintype "passive"))
    )
    (net (code "27") (name "DIN2_C") (class "Default")
      (node (ref "JP6") (pin "3") (pinfunction "3_3") (pintype "passive"))
      (node (ref "X17") (pin "1") (pinfunction "S_1") (pintype "passive"))
    )
    (net (code "28") (name "DIN2_D") (class "Default")
      (node (ref "JP8") (pin "3") (pinfunction "3_3") (pintype "passive"))
      (node (ref "X23") (pin "1") (pinfunction "S_1") (pintype "passive"))
    )
    (net (code "29") (name "GND") (class "Default")
      (node (ref "C1") (pin "-") (pinfunction "-_-") (pintype "passive"))
      (node (ref "C15") (pin "-") (pinfunction "-_-") (pintype "passive"))
      (node (ref "C22") (pin "-") (pinfunction "-_-") (pintype "passive"))
      (node (ref "C8") (pin "-") (pinfunction "-_-") (pintype "passive"))
      (node (ref "D1") (pin "A") (pinfunction "A_A") (pintype "passive"))
      (node (ref "D2") (pin "3") (pinfunction "3_3") (pintype "passive"))
      (node (ref "D3") (pin "A") (pinfunction "A_A") (pintype "passive"))
      (node (ref "D4") (pin "3") (pinfunction "3_3") (pintype "passive"))
      (node (ref "D5") (pin "A") (pinfunction "A_A") (pintype "passive"))
      (node (ref "D6") (pin "3") (pinfunction "3_3") (pintype "passive"))
      (node (ref "D7") (pin "A") (pinfunction "A_A") (pintype "passive"))
      (node (ref "D8") (pin "3") (pinfunction "3_3") (pintype "passive"))
      (node (ref "JP1") (pin "5") (pinfunction "5_5") (pintype "passive"))
      (node (ref "JP2") (pin "5") (pinfunction "5_5") (pintype "passive"))
      (node (ref "JP3") (pin "5") (pinfunction "5_5") (pintype "passive"))
      (node (ref "JP4") (pin "5") (pinfunction "5_5") (pintype "passive"))
      (node (ref "JP5") (pin "5") (pinfunction "5_5") (pintype "passive"))
      (node (ref "JP6") (pin "5") (pinfunction "5_5") (pintype "passive"))
      (node (ref "JP7") (pin "5") (pinfunction "5_5") (pintype "passive"))
      (node (ref "JP8") (pin "5") (pinfunction "5_5") (pintype "passive"))
      (node (ref "U1") (pin "2") (pinfunction "2_2") (pintype "passive"))
      (node (ref "U1") (pin "5") (pinfunction "5_5") (pintype "passive"))
      (node (ref "U2") (pin "2") (pinfunction "2_2") (pintype "passive"))
      (node (ref "U2") (pin "5") (pinfunction "5_5") (pintype "passive"))
      (node (ref "U3") (pin "2") (pinfunction "2_2") (pintype "passive"))
      (node (ref "U3") (pin "5") (pinfunction "5_5") (pintype "passive"))
      (node (ref "U4") (pin "2") (pinfunction "2_2") (pintype "passive"))
      (node (ref "U4") (pin "5") (pinfunction "5_5") (pintype "passive"))
      (node (ref "X1") (pin "2") (pinfunction "K_2") (pintype "passive"))
      (node (ref "X10") (pin "3") (pinfunction "3_3") (pintype "bidirectional"))
      (node (ref "X12") (pin "2") (pinfunction "S_2") (pintype "passive"))
      (node (ref "X15") (pin "5") (pinfunction "S_5") (pintype "passive"))
      (node (ref "X16") (pin "3") (pinfunction "3_3") (pintype "bidirectional"))
      (node (ref "X18") (pin "2") (pinfunction "S_2") (pintype "passive"))
      (node (ref "X21") (pin "5") (pinfunction "S_5") (pintype "passive"))
      (node (ref "X22") (pin "3") (pinfunction "3_3") (pintype "bidirectional"))
      (node (ref "X24") (pin "2") (pinfunction "S_2") (pintype "passive"))
      (node (ref "X3") (pin "5") (pinfunction "S_5") (pintype "passive"))
      (node (ref "X4") (pin "3") (pinfunction "3_3") (pintype "bidirectional"))
      (node (ref "X6") (pin "2") (pinfunction "S_2") (pintype "passive"))
      (node (ref "X9") (pin "5") (pinfunction "S_5") (pintype "passive"))
    )
    (net (code "30") (name "HS1_A") (class "Default")
      (node (ref "JP1") (pin "7") (pinfunction "7_7") (pintype "passive"))
      (node (ref "X3") (pin "1") (pinfunction "S_1") (pintype "passive"))
    )
    (net (code "31") (name "HS1_B") (class "Default")
      (node (ref "JP3") (pin "7") (pinfunction "7_7") (pintype "passive"))
      (node (ref "X9") (pin "1") (pinfunction "S_1") (pintype "passive"))
    )
    (net (code "32") (name "HS1_C") (class "Default")
      (node (ref "JP5") (pin "7") (pinfunction "7_7") (pintype "passive"))
      (node (ref "X15") (pin "1") (pinfunction "S_1") (pintype "passive"))
    )
    (net (code "33") (name "HS1_D") (class "Default")
      (node (ref "JP7") (pin "7") (pinfunction "7_7") (pintype "passive"))
      (node (ref "X21") (pin "1") (pinfunction "S_1") (pintype "passive"))
    )
    (net (code "34") (name "HS2_A") (class "Default")
      (node (ref "JP1") (pin "8") (pinfunction "8_8") (pintype "passive"))
      (node (ref "X3") (pin "2") (pinfunction "S_2") (pintype "passive"))
    )
    (net (code "35") (name "HS2_B") (class "Default")
      (node (ref "JP3") (pin "8") (pinfunction "8_8") (pintype "passive"))
      (node (ref "X9") (pin "2") (pinfunction "S_2") (pintype "passive"))
    )
    (net (code "36") (name "HS2_C") (class "Default")
      (node (ref "JP5") (pin "8") (pinfunction "8_8") (pintype "passive"))
      (node (ref "X15") (pin "2") (pinfunction "S_2") (pintype "passive"))
    )
    (net (code "37") (name "HS2_D") (class "Default")
      (node (ref "JP7") (pin "8") (pinfunction "8_8") (pintype "passive"))
      (node (ref "X21") (pin "2") (pinfunction "S_2") (pintype "passive"))
    )
    (net (code "38") (name "HS3_A") (class "Default")
      (node (ref "JP1") (pin "9") (pinfunction "9_9") (pintype "passive"))
      (node (ref "X3") (pin "3") (pinfunction "S_3") (pintype "passive"))
    )
    (net (code "39") (name "HS3_B") (class "Default")
      (node (ref "JP3") (pin "9") (pinfunction "9_9") (pintype "passive"))
      (node (ref "X9") (pin "3") (pinfunction "S_3") (pintype "passive"))
    )
    (net (code "40") (name "HS3_C") (class "Default")
      (node (ref "JP5") (pin "9") (pinfunction "9_9") (pintype "passive"))
      (node (ref "X15") (pin "3") (pinfunction "S_3") (pintype "passive"))
    )
    (net (code "41") (name "HS3_D") (class "Default")
      (node (ref "JP7") (pin "9") (pinfunction "9_9") (pintype "passive"))
      (node (ref "X21") (pin "3") (pinfunction "S_3") (pintype "passive"))
    )
    (net (code "42") (name "MW1_A") (class "Default")
      (node (ref "C2") (pin "1") (pinfunction "1_1") (pintype "passive"))
      (node (ref "C5") (pin "1") (pinfunction "1_1") (pintype "passive"))
      (node (ref "L1") (pin "2") (pinfunction "2_2") (pintype "passive"))
      (node (ref "X2") (pin "1") (pinfunction "S_1") (pintype "passive"))
    )
    (net (code "43") (name "MW1_B") (class "Default")
      (node (ref "C12") (pin "1") (pinfunction "1_1") (pintype "passive"))
      (node (ref "C9") (pin "1") (pinfunction "1_1") (pintype "passive"))
      (node (ref "L4") (pin "2") (pinfunction "2_2") (pintype "passive"))
      (node (ref "X8") (pin "1") (pinfunction "S_1") (pintype "passive"))
    )
    (net (code "44") (name "MW1_C") (class "Default")
      (node (ref "C16") (pin "1") (pinfunction "1_1") (pintype "passive"))
      (node (ref "C19") (pin "1") (pinfunction "1_1") (pintype "passive"))
      (node (ref "L7") (pin "2") (pinfunction "2_2") (pintype "passive"))
      (node (ref "X14") (pin "1") (pinfunction "S_1") (pintype "passive"))
    )
    (net (code "45") (name "MW1_D") (class "Default")
      (node (ref "C23") (pin "1") (pinfunction "1_1") (pintype "passive"))
      (node (ref "C24") (pin "1") (pinfunction "1_1") (pintype "passive"))
      (node (ref "L10") (pin "2") (pinfunction "2_2") (pintype "passive"))
      (node (ref "X20") (pin "1") (pinfunction "S_1") (pintype "passive"))
    )
    (net (code "46") (name "MW2_A") (class "Default")
      (node (ref "C3") (pin "1") (pinfunction "1_1") (pintype "passive"))
      (node (ref "C6") (pin "1") (pinfunction "1_1") (pintype "passive"))
      (node (ref "L2") (pin "2") (pinfunction "2_2") (pintype "passive"))
      (node (ref "X2") (pin "2") (pinfunction "S_2") (pintype "passive"))
    )
    (net (code "47") (name "MW2_B") (class "Default")
      (node (ref "C10") (pin "1") (pinfunction "1_1") (pintype "passive"))
      (node (ref "C13") (pin "1") (pinfunction "1_1") (pintype "passive"))
      (node (ref "L5") (pin "2") (pinfunction "2_2") (pintype "passive"))
      (node (ref "X8") (pin "2") (pinfunction "S_2") (pintype "passive"))
    )
    (net (code "48") (name "MW2_C") (class "Default")
      (node (ref "C17") (pin "1") (pinfunction "1_1") (pintype "passive"))
      (node (ref "C20") (pin "1") (pinfunction "1_1") (pintype "passive"))
      (node (ref "L8") (pin "2") (pinfunction "2_2") (pintype "passive"))
      (node (ref "X14") (pin "2") (pinfunction "S_2") (pintype "passive"))
    )
    (net (code "49") (name "MW2_D") (class "Default")
      (node (ref "C25") (pin "1") (pinfunction "1_1") (pintype "passive"))
      (node (ref "C26") (pin "1") (pinfunction "1_1") (pintype "passive"))
      (node (ref "L11") (pin "2") (pinfunction "2_2") (pintype "passive"))
      (node (ref "X20") (pin "2") (pinfunction "S_2") (pintype "passive"))
    )
    (net (code "50") (name "MW3_A") (class "Default")
      (node (ref "C4") (pin "1") (pinfunction "1_1") (pintype "passive"))
      (node (ref "C7") (pin "1") (pinfunction "1_1") (pintype "passive"))
      (node (ref "L3") (pin "2") (pinfunction "2_2") (pintype "passive"))
      (node (ref "X2") (pin "3") (pinfunction "S_3") (pintype "passive"))
    )
    (net (code "51") (name "MW3_B") (class "Default")
      (node (ref "C11") (pin "1") (pinfunction "1_1") (pintype "passive"))
      (node (ref "C14") (pin "1") (pinfunction "1_1") (pintype "passive"))
      (node (ref "L6") (pin "2") (pinfunction "2_2") (pintype "passive"))
      (node (ref "X8") (pin "3") (pinfunction "S_3") (pintype "passive"))
    )
    (net (code "52") (name "MW3_C") (class "Default")
      (node (ref "C18") (pin "1") (pinfunction "1_1") (pintype "passive"))
      (node (ref "C21") (pin "1") (pinfunction "1_1") (pintype "passive"))
      (node (ref "L9") (pin "2") (pinfunction "2_2") (pintype "passive"))
      (node (ref "X14") (pin "3") (pinfunction "S_3") (pintype "passive"))
    )
    (net (code "53") (name "MW3_D") (class "Default")
      (node (ref "C27") (pin "1") (pinfunction "1_1") (pintype "passive"))
      (node (ref "C28") (pin "1") (pinfunction "1_1") (pintype "passive"))
      (node (ref "L12") (pin "2") (pinfunction "2_2") (pintype "passive"))
      (node (ref "X20") (pin "3") (pinfunction "S_3") (pintype "passive"))
    )
    (net (code "54") (name "Net-(C2-Pad2)") (class "Default")
      (node (ref "C2") (pin "2") (pinfunction "2_2") (pintype "passive"))
      (node (ref "R1") (pin "1") (pinfunction "1_1") (pintype "passive"))
    )
    (net (code "55") (name "Net-(C3-Pad2)") (class "Default")
      (node (ref "C3") (pin "2") (pinfunction "2_2") (pintype "passive"))
      (node (ref "R2") (pin "1") (pinfunction "1_1") (pintype "passive"))
    )
    (net (code "56") (name "Net-(C4-Pad2)") (class "Default")
      (node (ref "C4") (pin "2") (pinfunction "2_2") (pintype "passive"))
      (node (ref "R3") (pin "1") (pinfunction "1_1") (pintype "passive"))
    )
    (net (code "57") (name "Net-(C5-Pad2)") (class "Default")
      (node (ref "C5") (pin "2") (pinfunction "2_2") (pintype "passive"))
      (node (ref "R1") (pin "2") (pinfunction "2_2") (pintype "passive"))
    )
    (net (code "58") (name "Net-(C6-Pad2)") (class "Default")
      (node (ref "C6") (pin "2") (pinfunction "2_2") (pintype "passive"))
      (node (ref "R2") (pin "2") (pinfunction "2_2") (pintype "passive"))
    )
    (net (code "59") (name "Net-(C7-Pad2)") (class "Default")
      (node (ref "C7") (pin "2") (pinfunction "2_2") (pintype "passive"))
      (node (ref "R3") (pin "2") (pinfunction "2_2") (pintype "passive"))
    )
    (net (code "60") (name "Net-(C9-Pad2)") (class "Default")
      (node (ref "C9") (pin "2") (pinfunction "2_2") (pintype "passive"))
      (node (ref "R4") (pin "1") (pinfunction "1_1") (pintype "passive"))
    )
    (net (code "61") (name "Net-(C10-Pad2)") (class "Default")
      (node (ref "C10") (pin "2") (pinfunction "2_2") (pintype "passive"))
      (node (ref "R5") (pin "1") (pinfunction "1_1") (pintype "passive"))
    )
    (net (code "62") (name "Net-(C11-Pad2)") (class "Default")
      (node (ref "C11") (pin "2") (pinfunction "2_2") (pintype "passive"))
      (node (ref "R6") (pin "1") (pinfunction "1_1") (pintype "passive"))
    )
    (net (code "63") (name "Net-(C12-Pad2)") (class "Default")
      (node (ref "C12") (pin "2") (pinfunction "2_2") (pintype "passive"))
      (node (ref "R4") (pin "2") (pinfunction "2_2") (pintype "passive"))
    )
    (net (code "64") (name "Net-(C13-Pad2)") (class "Default")
      (node (ref "C13") (pin "2") (pinfunction "2_2") (pintype "passive"))
      (node (ref "R5") (pin "2") (pinfunction "2_2") (pintype "passive"))
    )
    (net (code "65") (name "Net-(C14-Pad2)") (class "Default")
      (node (ref "C14") (pin "2") (pinfunction "2_2") (pintype "passive"))
      (node (ref "R6") (pin "2") (pinfunction "2_2") (pintype "passive"))
    )
    (net (code "66") (name "Net-(C16-Pad2)") (class "Default")
      (node (ref "C16") (pin "2") (pinfunction "2_2") (pintype "passive"))
      (node (ref "R7") (pin "1") (pinfunction "1_1") (pintype "passive"))
    )
    (net (code "67") (name "Net-(C17-Pad2)") (class "Default")
      (node (ref "C17") (pin "2") (pinfunction "2_2") (pintype "passive"))
      (node (ref "R8") (pin "1") (pinfunction "1_1") (pintype "passive"))
    )
    (net (code "68") (name "Net-(C18-Pad2)") (class "Default")
      (node (ref "C18") (pin "2") (pinfunction "2_2") (pintype "passive"))
      (node (ref "R9") (pin "1") (pinfunction "1_1") (pintype "passive"))
    )
    (net (code "69") (name "Net-(C19-Pad2)") (class "Default")
      (node (ref "C19") (pin "2") (pinfunction "2_2") (pintype "passive"))
      (node (ref "R7") (pin "2") (pinfunction "2_2") (pintype "passive"))
    )
    (net (code "70") (name "Net-(C20-Pad2)") (class "Default")
      (node (ref "C20") (pin "2") (pinfunction "2_2") (pintype "passive"))
      (node (ref "R8") (pin "2") (pinfunction "2_2") (pintype "passive"))
    )
    (net (code "71") (name "Net-(C21-Pad2)") (class "Default")
      (node (ref "C21") (pin "2") (pinfunction "2_2") (pintype "passive"))
      (node (ref "R9") (pin "2") (pinfunction "2_2") (pintype "passive"))
    )
    (net (code "72") (name "Net-(C23-Pad2)") (class "Default")
      (node (ref "C23") (pin "2") (pinfunction "2_2") (pintype "passive"))
      (node (ref "R10") (pin "1") (pinfunction "1_1") (pintype "passive"))
    )
    (net (code "73") (name "Net-(C24-Pad2)") (class "Default")
      (node (ref "C24") (pin "2") (pinfunction "2_2") (pintype "passive"))
      (node (ref "R10") (pin "2") (pinfunction "2_2") (pintype "passive"))
    )
    (net (code "74") (name "Net-(C25-Pad2)") (class "Default")
      (node (ref "C25") (pin "2") (pinfunction "2_2") (pintype "passive"))
      (node (ref "R11") (pin "1") (pinfunction "1_1") (pintype "passive"))
    )
    (net (code "75") (name "Net-(C26-Pad2)") (class "Default")
      (node (ref "C26") (pin "2") (pinfunction "2_2") (pintype "passive"))
      (node (ref "R11") (pin "2") (pinfunction "2_2") (pintype "passive"))
    )
    (net (code "76") (name "Net-(C27-Pad2)") (class "Default")
      (node (ref "C27") (pin "2") (pinfunction "2_2") (pintype "passive"))
      (node (ref "R12") (pin "1") (pinfunction "1_1") (pintype "passive"))
    )
    (net (code "77") (name "Net-(C28-Pad2)") (class "Default")
      (node (ref "C28") (pin "2") (pinfunction "2_2") (pintype "passive"))
      (node (ref "R12") (pin "2") (pinfunction "2_2") (pintype "passive"))
    )
    (net (code "78") (name "VCC") (class "Default")
      (node (ref "F1") (pin "1") (pinfunction "1_1") (pintype "passive"))
      (node (ref "F2") (pin "1") (pinfunction "1_1") (pintype "passive"))
      (node (ref "F3") (pin "1") (pinfunction "1_1") (pintype "passive"))
      (node (ref "F4") (pin "1") (pinfunction "1_1") (pintype "passive"))
      (node (ref "X1") (pin "1") (pinfunction "K_1") (pintype "passive"))
    )
    (net (code "79") (name "VDD_A") (class "Default")
      (node (ref "C1") (pin "+") (pinfunction "+_+") (pintype "passive"))
      (node (ref "D1") (pin "C") (pinfunction "C_C") (pintype "passive"))
      (node (ref "F1") (pin "2") (pinfunction "2_2") (pintype "passive"))
      (node (ref "JP1") (pin "4") (pinfunction "4_4") (pintype "passive"))
    )
    (net (code "80") (name "VDD_B") (class "Default")
      (node (ref "C8") (pin "+") (pinfunction "+_+") (pintype "passive"))
      (node (ref "D3") (pin "C") (pinfunction "C_C") (pintype "passive"))
      (node (ref "F2") (pin "2") (pinfunction "2_2") (pintype "passive"))
      (node (ref "JP3") (pin "4") (pinfunction "4_4") (pintype "passive"))
    )
    (net (code "81") (name "VDD_C") (class "Default")
      (node (ref "C15") (pin "+") (pinfunction "+_+") (pintype "passive"))
      (node (ref "D5") (pin "C") (pinfunction "C_C") (pintype "passive"))
      (node (ref "F3") (pin "2") (pinfunction "2_2") (pintype "passive"))
      (node (ref "JP5") (pin "4") (pinfunction "4_4") (pintype "passive"))
    )
    (net (code "82") (name "VDD_D") (class "Default")
      (node (ref "C22") (pin "+") (pinfunction "+_+") (pintype "passive"))
      (node (ref "D7") (pin "C") (pinfunction "C_C") (pintype "passive"))
      (node (ref "F4") (pin "2") (pinfunction "2_2") (pintype "passive"))
      (node (ref "JP7") (pin "4") (pinfunction "4_4") (pintype "passive"))
    )
    (net (code "83") (name "unconnected-(JP2-Pad1)") (class "Default")
      (node (ref "JP2") (pin "1") (pinfunction "1_1") (pintype "passive"))
    )
    (net (code "84") (name "unconnected-(JP2-Pad2)") (class "Default")
      (node (ref "JP2") (pin "2") (pinfunction "2_2") (pintype "passive"))
    )
    (net (code "85") (name "unconnected-(JP2-Pad6)") (class "Default")
      (node (ref "JP2") (pin "6") (pinfunction "6_6") (pintype "passive"))
    )
    (net (code "86") (name "unconnected-(JP2-Pad7)") (class "Default")
      (node (ref "JP2") (pin "7") (pinfunction "7_7") (pintype "passive"))
    )
    (net (code "87") (name "unconnected-(JP2-Pad8)") (class "Default")
      (node (ref "JP2") (pin "8") (pinfunction "8_8") (pintype "passive"))
    )
    (net (code "88") (name "unconnected-(JP2-Pad9)") (class "Default")
      (node (ref "JP2") (pin "9") (pinfunction "9_9") (pintype "passive"))
    )
    (net (code "89") (name "unconnected-(JP4-Pad1)") (class "Default")
      (node (ref "JP4") (pin "1") (pinfunction "1_1") (pintype "passive"))
    )
    (net (code "90") (name "unconnected-(JP4-Pad2)") (class "Default")
      (node (ref "JP4") (pin "2") (pinfunction "2_2") (pintype "passive"))
    )
    (net (code "91") (name "unconnected-(JP4-Pad6)") (class "Default")
      (node (ref "JP4") (pin "6") (pinfunction "6_6") (pintype "passive"))
    )
    (net (code "92") (name "unconnected-(JP4-Pad7)") (class "Default")
      (node (ref "JP4") (pin "7") (pinfunction "7_7") (pintype "passive"))
    )
    (net (code "93") (name "unconnected-(JP4-Pad8)") (class "Default")
      (node (ref "JP4") (pin "8") (pinfunction "8_8") (pintype "passive"))
    )
    (net (code "94") (name "unconnected-(JP4-Pad9)") (class "Default")
      (node (ref "JP4") (pin "9") (pinfunction "9_9") (pintype "passive"))
    )
    (net (code "95") (name "unconnected-(JP6-Pad1)") (class "Default")
      (node (ref "JP6") (pin "1") (pinfunction "1_1") (pintype "passive"))
    )
    (net (code "96") (name "unconnected-(JP6-Pad2)") (class "Default")
      (node (ref "JP6") (pin "2") (pinfunction "2_2") (pintype "passive"))
    )
    (net (code "97") (name "unconnected-(JP6-Pad6)") (class "Default")
      (node (ref "JP6") (pin "6") (pinfunction "6_6") (pintype "passive"))
    )
    (net (code "98") (name "unconnected-(JP6-Pad7)") (class "Default")
      (node (ref "JP6") (pin "7") (pinfunction "7_7") (pintype "passive"))
    )
    (net (code "99") (name "unconnected-(JP6-Pad8)") (class "Default")
      (node (ref "JP6") (pin "8") (pinfunction "8_8") (pintype "passive"))
    )
    (net (code "100") (name "unconnected-(JP6-Pad9)") (class "Default")
      (node (ref "JP6") (pin "9") (pinfunction "9_9") (pintype "passive"))
    )
    (net (code "101") (name "unconnected-(JP8-Pad1)") (class "Default")
      (node (ref "JP8") (pin "1") (pinfunction "1_1") (pintype "passive"))
    )
    (net (code "102") (name "unconnected-(JP8-Pad2)") (class "Default")
      (node (ref "JP8") (pin "2") (pinfunction "2_2") (pintype "passive"))
    )
    (net (code "103") (name "unconnected-(JP8-Pad6)") (class "Default")
      (node (ref "JP8") (pin "6") (pinfunction "6_6") (pintype "passive"))
    )
    (net (code "104") (name "unconnected-(JP8-Pad7)") (class "Default")
      (node (ref "JP8") (pin "7") (pinfunction "7_7") (pintype "passive"))
    )
    (net (code "105") (name "unconnected-(JP8-Pad8)") (class "Default")
      (node (ref "JP8") (pin "8") (pinfunction "8_8") (pintype "passive"))
    )
    (net (code "106") (name "unconnected-(JP8-Pad9)") (class "Default")
      (node (ref "JP8") (pin "9") (pinfunction "9_9") (pintype "passive"))
    )
    (net (code "107") (name "unconnected-(X4-Pad1)") (class "Default")
      (node (ref "X4") (pin "1") (pinfunction "1_1") (pintype "bidirectional"))
    )
    (net (code "108") (name "unconnected-(X4-Pad4)") (class "Default")
      (node (ref "X4") (pin "4") (pinfunction "4_4") (pintype "bidirectional"))
    )
    (net (code "109") (name "unconnected-(X4-Pad9)") (class "Default")
      (node (ref "X4") (pin "9") (pinfunction "9_9") (pintype "bidirectional"))
    )
    (net (code "110") (name "unconnected-(X4-Pad10)") (class "Default")
      (node (ref "X4") (pin "10") (pinfunction "10_10") (pintype "bidirectional"))
    )
    (net (code "111") (name "unconnected-(X10-Pad1)") (class "Default")
      (node (ref "X10") (pin "1") (pinfunction "1_1") (pintype "bidirectional"))
    )
    (net (code "112") (name "unconnected-(X10-Pad4)") (class "Default")
      (node (ref "X10") (pin "4") (pinfunction "4_4") (pintype "bidirectional"))
    )
    (net (code "113") (name "unconnected-(X10-Pad9)") (class "Default")
      (node (ref "X10") (pin "9") (pinfunction "9_9") (pintype "bidirectional"))
    )
    (net (code "114") (name "unconnected-(X10-Pad10)") (class "Default")
      (node (ref "X10") (pin "10") (pinfunction "10_10") (pintype "bidirectional"))
    )
    (net (code "115") (name "unconnected-(X16-Pad1)") (class "Default")
      (node (ref "X16") (pin "1") (pinfunction "1_1") (pintype "bidirectional"))
    )
    (net (code "116") (name "unconnected-(X16-Pad4)") (class "Default")
      (node (ref "X16") (pin "4") (pinfunction "4_4") (pintype "bidirectional"))
    )
    (net (code "117") (name "unconnected-(X16-Pad9)") (class "Default")
      (node (ref "X16") (pin "9") (pinfunction "9_9") (pintype "bidirectional"))
    )
    (net (code "118") (name "unconnected-(X16-Pad10)") (class "Default")
      (node (ref "X16") (pin "10") (pinfunction "10_10") (pintype "bidirectional"))
    )
    (net (code "119") (name "unconnected-(X22-Pad1)") (class "Default")
      (node (ref "X22") (pin "1") (pinfunction "1_1") (pintype "bidirectional"))
    )
    (net (code "120") (name "unconnected-(X22-Pad4)") (class "Default")
      (node (ref "X22") (pin "4") (pinfunction "4_4") (pintype "bidirectional"))
    )
    (net (code "121") (name "unconnected-(X22-Pad9)") (class "Default")
      (node (ref "X22") (pin "9") (pinfunction "9_9") (pintype "bidirectional"))
    )
    (net (code "122") (name "unconnected-(X22-Pad10)") (class "Default")
      (node (ref "X22") (pin "10") (pinfunction "10_10") (pintype "bidirectional"))
    )
    (net (code "123") (name "~{CHA_A}") (class "Default")
      (node (ref "JP1") (pin "11") (pinfunction "11_11") (pintype "passive"))
      (node (ref "U1") (pin "3") (pinfunction "3_3") (pintype "passive"))
      (node (ref "X4") (pin "5") (pinfunction "5_5") (pintype "bidirectional"))
      (node (ref "X7") (pin "3") (pinfunction "S_3") (pintype "passive"))
    )
    (net (code "124") (name "~{CHA_B}") (class "Default")
      (node (ref "JP3") (pin "11") (pinfunction "11_11") (pintype "passive"))
      (node (ref "U2") (pin "3") (pinfunction "3_3") (pintype "passive"))
      (node (ref "X10") (pin "5") (pinfunction "5_5") (pintype "bidirectional"))
      (node (ref "X13") (pin "3") (pinfunction "S_3") (pintype "passive"))
    )
    (net (code "125") (name "~{CHA_C}") (class "Default")
      (node (ref "JP5") (pin "11") (pinfunction "11_11") (pintype "passive"))
      (node (ref "U3") (pin "3") (pinfunction "3_3") (pintype "passive"))
      (node (ref "X16") (pin "5") (pinfunction "5_5") (pintype "bidirectional"))
      (node (ref "X19") (pin "3") (pinfunction "S_3") (pintype "passive"))
    )
    (net (code "126") (name "~{CHA_D}") (class "Default")
      (node (ref "JP7") (pin "11") (pinfunction "11_11") (pintype "passive"))
      (node (ref "U4") (pin "3") (pinfunction "3_3") (pintype "passive"))
      (node (ref "X22") (pin "5") (pinfunction "5_5") (pintype "bidirectional"))
      (node (ref "X25") (pin "3") (pinfunction "S_3") (pintype "passive"))
    )
    (net (code "127") (name "~{CHB_A}") (class "Default")
      (node (ref "JP1") (pin "13") (pinfunction "13_13") (pintype "passive"))
      (node (ref "U1") (pin "6") (pinfunction "6_6") (pintype "passive"))
      (node (ref "X4") (pin "7") (pinfunction "7_7") (pintype "bidirectional"))
      (node (ref "X7") (pin "1") (pinfunction "S_1") (pintype "passive"))
    )
    (net (code "128") (name "~{CHB_B}") (class "Default")
      (node (ref "JP3") (pin "13") (pinfunction "13_13") (pintype "passive"))
      (node (ref "U2") (pin "6") (pinfunction "6_6") (pintype "passive"))
      (node (ref "X10") (pin "7") (pinfunction "7_7") (pintype "bidirectional"))
      (node (ref "X13") (pin "1") (pinfunction "S_1") (pintype "passive"))
    )
    (net (code "129") (name "~{CHB_C}") (class "Default")
      (node (ref "JP5") (pin "13") (pinfunction "13_13") (pintype "passive"))
      (node (ref "U3") (pin "6") (pinfunction "6_6") (pintype "passive"))
      (node (ref "X16") (pin "7") (pinfunction "7_7") (pintype "bidirectional"))
      (node (ref "X19") (pin "1") (pinfunction "S_1") (pintype "passive"))
    )
    (net (code "130") (name "~{CHB_D}") (class "Default")
      (node (ref "JP7") (pin "13") (pinfunction "13_13") (pintype "passive"))
      (node (ref "U4") (pin "6") (pinfunction "6_6") (pintype "passive"))
      (node (ref "X22") (pin "7") (pinfunction "7_7") (pintype "bidirectional"))
      (node (ref "X25") (pin "1") (pinfunction "S_1") (pintype "passive"))
    )
    (net (code "131") (name "~{MW1_A}") (class "Default")
      (node (ref "JP1") (pin "1") (pinfunction "1_1") (pintype "passive"))
      (node (ref "L1") (pin "1") (pinfunction "1_1") (pintype "passive"))
    )
    (net (code "132") (name "~{MW1_B}") (class "Default")
      (node (ref "JP3") (pin "1") (pinfunction "1_1") (pintype "passive"))
      (node (ref "L4") (pin "1") (pinfunction "1_1") (pintype "passive"))
    )
    (net (code "133") (name "~{MW1_C}") (class "Default")
      (node (ref "JP5") (pin "1") (pinfunction "1_1") (pintype "passive"))
      (node (ref "L7") (pin "1") (pinfunction "1_1") (pintype "passive"))
    )
    (net (code "134") (name "~{MW1_D}") (class "Default")
      (node (ref "JP7") (pin "1") (pinfunction "1_1") (pintype "passive"))
      (node (ref "L10") (pin "1") (pinfunction "1_1") (pintype "passive"))
    )
    (net (code "135") (name "~{MW2_A}") (class "Default")
      (node (ref "JP1") (pin "2") (pinfunction "2_2") (pintype "passive"))
      (node (ref "L2") (pin "1") (pinfunction "1_1") (pintype "passive"))
    )
    (net (code "136") (name "~{MW2_B}") (class "Default")
      (node (ref "JP3") (pin "2") (pinfunction "2_2") (pintype "passive"))
      (node (ref "L5") (pin "1") (pinfunction "1_1") (pintype "passive"))
    )
    (net (code "137") (name "~{MW2_C}") (class "Default")
      (node (ref "JP5") (pin "2") (pinfunction "2_2") (pintype "passive"))
      (node (ref "L8") (pin "1") (pinfunction "1_1") (pintype "passive"))
    )
    (net (code "138") (name "~{MW2_D}") (class "Default")
      (node (ref "JP7") (pin "2") (pinfunction "2_2") (pintype "passive"))
      (node (ref "L11") (pin "1") (pinfunction "1_1") (pintype "passive"))
    )
    (net (code "139") (name "~{MW3_A}") (class "Default")
      (node (ref "JP1") (pin "3") (pinfunction "3_3") (pintype "passive"))
      (node (ref "L3") (pin "1") (pinfunction "1_1") (pintype "passive"))
    )
    (net (code "140") (name "~{MW3_B}") (class "Default")
      (node (ref "JP3") (pin "3") (pinfunction "3_3") (pintype "passive"))
      (node (ref "L6") (pin "1") (pinfunction "1_1") (pintype "passive"))
    )
    (net (code "141") (name "~{MW3_C}") (class "Default")
      (node (ref "JP5") (pin "3") (pinfunction "3_3") (pintype "passive"))
      (node (ref "L9") (pin "1") (pinfunction "1_1") (pintype "passive"))
    )
    (net (code "142") (name "~{MW3_D}") (class "Default")
      (node (ref "JP7") (pin "3") (pinfunction "3_3") (pintype "passive"))
      (node (ref "L12") (pin "1") (pinfunction "1_1") (pintype "passive"))
    )
  )
)
